# RSheet2.net
KiCad netlist of a schematic drawn in Altium Designer
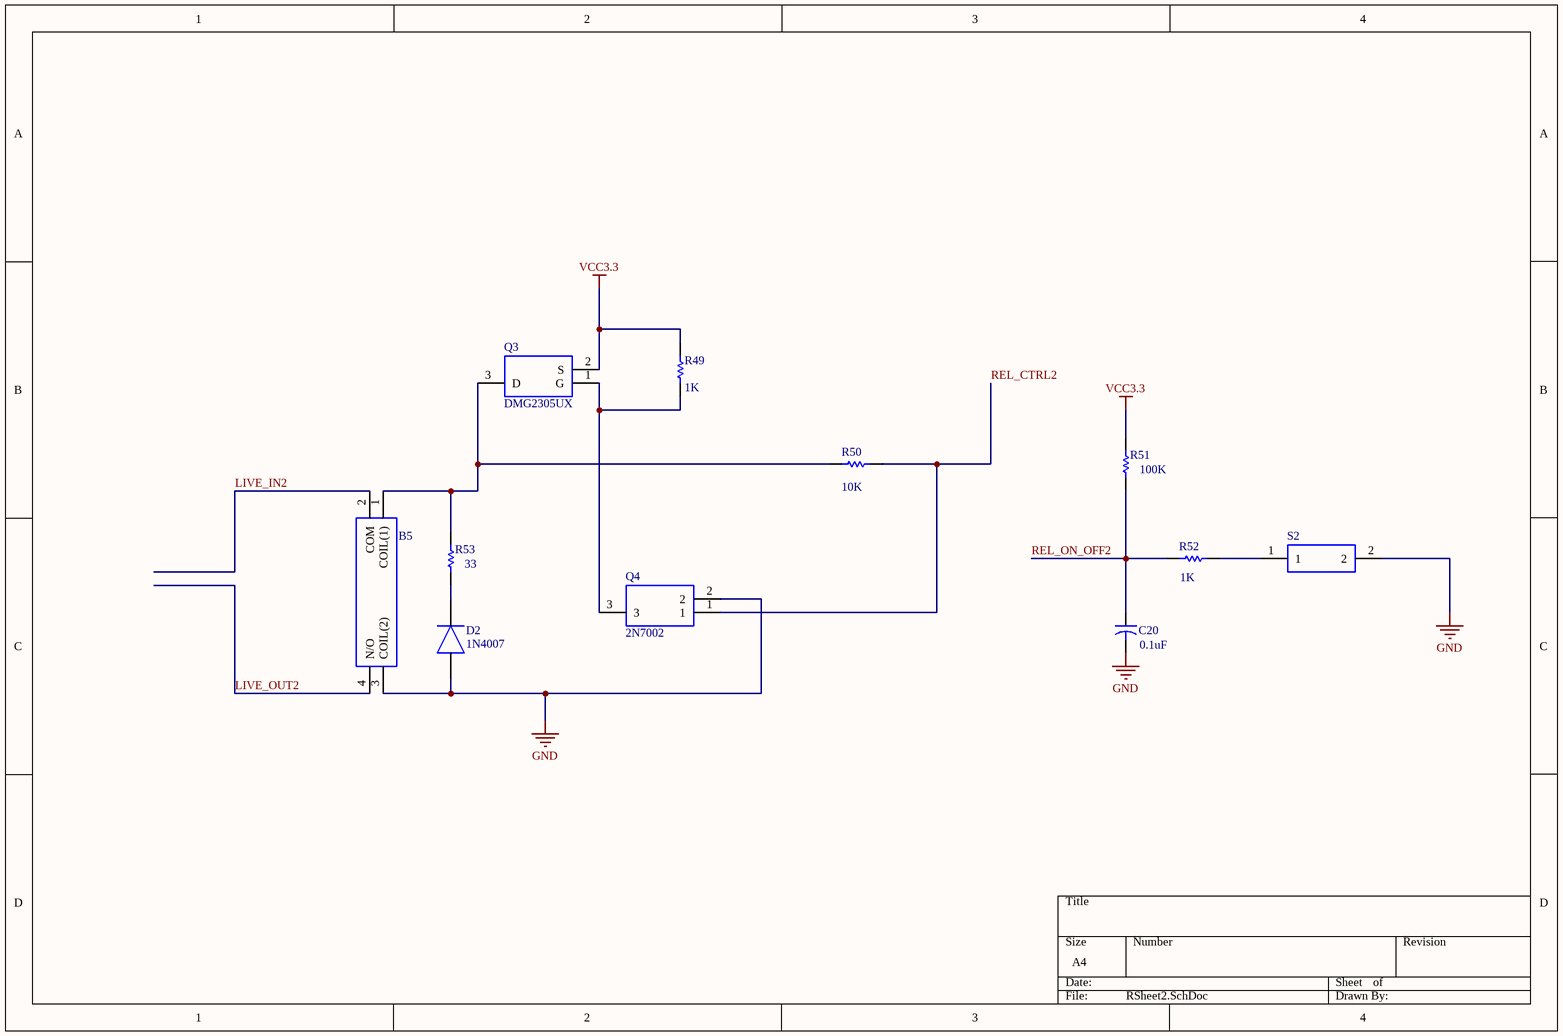
[diagram p0: RSheet2.SchDoc]

(export (version "E")
  (design (tool "Eeschema 10.0.6"))
  (components
    (comp (ref "B5")
      (value "HF3FA_005-HTF")
      (footprint "HF3FA005HTF:HF3FA005HTF")
      (description "Subminiature high power relay. 10A 5V.")
      (fields (field (name "MANUFACTURER_PART_NUMBER") "HF3FA/005-HTF"))
      (libsource (lib "HF3FA_005-HTF") (part "HF3FA_005-HTF"))
    )
    (comp (ref "C20")
      (value "0.1uF")
      (footprint "RESC0603X26N:RESC0603X26N")
      (description "Capacitor")
      (fields (field (name "Comment") "Cap2") (field (name "PUBLISHER") "Altium Limited"))
      (libsource (lib "Miscellaneous Devices") (part "Cap2"))
    )
    (comp (ref "D2")
      (value "1N4007")
      (footprint "DIOAD1408W86L464D236:DIOAD1408W86L464D236")
      (description "Diode Standard 1A 1000V 1Vf DO41 Diodes Inc 1N4007-T, Switching Diode, 1000V 1A, 2-Pin DO-41")
      (fields (field (name "RS PART NUMBER") "7384724P") (field (name "MANUFACTURER_PART_NUMBER") "1N4007-T"))
      (libsource (lib "1N4007-T") (part "1N4007-T"))
    )
    (comp (ref "Q3")
      (value "DMG2305UX")
      (footprint "SOT96P240X100-3N:SOT96P240X100-3N")
      (fields
        (field (name "RS PART NUMBER") "1219640")
        (field (name "MANUFACTURER_PART_NUMBER") "DMG2305UX-7")
      )
      (libsource (lib "DMG2305UX-7") (part "DMG2305UX-7"))
    )
    (comp (ref "Q4")
      (value "2N7002")
      (footprint "SOT95P230X110-3N:SOT95P230X110-3N")
      (fields
        (field (name "RS PART NUMBER") "1125526")
        (field (name "MANUFACTURER_PART_NUMBER") "2N7002,215")
      )
      (libsource (lib "2N7002_215") (part "2N7002_215"))
    )
    (comp (ref "R49")
      (value "1K")
      (footprint "AXIAL-0.3")
      (description "Resistor")
      (fields (field (name "Comment") "Res1") (field (name "PUBLISHER") "Altium Limited"))
      (libsource (lib "Miscellaneous Devices") (part "Res1"))
    )
    (comp (ref "R50")
      (value "10K")
      (footprint "AXIAL-0.3")
      (description "Resistor")
      (fields (field (name "Comment") "Res1") (field (name "PUBLISHER") "Altium Limited"))
      (libsource (lib "Miscellaneous Devices") (part "Res1"))
    )
    (comp (ref "R51")
      (value "100K")
      (footprint "RESC0603X26N:RESC0603X26N")
      (description "Resistor")
      (fields (field (name "Comment") "Res1") (field (name "PUBLISHER") "Altium Limited"))
      (libsource (lib "Miscellaneous Devices") (part "Res1"))
    )
    (comp (ref "R52")
      (value "1K")
      (footprint "RESC0603X26N:RESC0603X26N")
      (description "Resistor")
      (fields (field (name "Comment") "Res1") (field (name "PUBLISHER") "Altium Limited"))
      (libsource (lib "Miscellaneous Devices") (part "Res1"))
    )
    (comp (ref "R53")
      (value "33")
      (footprint "AXIAL-0.3")
      (description "Resistor")
      (fields (field (name "PUBLISHER") "Altium Limited"))
      (libsource (lib "Miscellaneous Devices") (part "Res1"))
    )
    (comp (ref "S2")
      (value "TL3330AF260QG")
      (footprint "SMD & J-Bend Tact Switch WS-TASV:434121043836")
      (description "Tactile Switches 50mA@12VDC 260g OF Silver contacts")
      (libsource (lib "TL3330AF260QG") (part "TL3330AF260QG"))
    )
  )
  (nets
    (net (code "1") (name "/LIVE_IN2") (class "Default")
      (node (ref "B5") (pin "2") (pinfunction "COM_2") (pintype "passive"))
    )
    (net (code "2") (name "/LIVE_OUT2") (class "Default")
      (node (ref "B5") (pin "4") (pinfunction "N/O_4") (pintype "passive"))
    )
    (net (code "3") (name "/REL_CTRL2") (class "Default")
      (node (ref "Q4") (pin "1") (pinfunction "1_1") (pintype "passive"))
      (node (ref "R50") (pin "2") (pinfunction "2_2") (pintype "passive"))
    )
    (net (code "4") (name "/REL_ON_OFF2") (class "Default")
      (node (ref "C20") (pin "1") (pinfunction "1_1") (pintype "passive"))
      (node (ref "R51") (pin "1") (pinfunction "1_1") (pintype "passive"))
      (node (ref "R52") (pin "1") (pinfunction "1_1") (pintype "passive"))
    )
    (net (code "5") (name "GND") (class "Default")
      (node (ref "B5") (pin "3") (pinfunction "COIL(2)_3") (pintype "passive"))
      (node (ref "C20") (pin "2") (pinfunction "2_2") (pintype "passive"))
      (node (ref "D2") (pin "2") (pinfunction "A_2") (pintype "passive"))
      (node (ref "Q4") (pin "2") (pinfunction "2_2") (pintype "passive"))
      (node (ref "S2") (pin "2") (pinfunction "2_2") (pintype "passive"))
    )
    (net (code "6") (name "Net-(B5-COIL(1))") (class "Default")
      (node (ref "B5") (pin "1") (pinfunction "COIL(1)_1") (pintype "passive"))
      (node (ref "Q3") (pin "3") (pinfunction "D_3") (pintype "passive"))
      (node (ref "R50") (pin "1") (pinfunction "1_1") (pintype "passive"))
      (node (ref "R53") (pin "2") (pinfunction "2_2") (pintype "passive"))
    )
    (net (code "7") (name "Net-(D2-K)") (class "Default")
      (node (ref "D2") (pin "1") (pinfunction "K_1") (pintype "passive"))
      (node (ref "R53") (pin "1") (pinfunction "1_1") (pintype "passive"))
    )
    (net (code "8") (name "Net-(Q3-G)") (class "Default")
      (node (ref "Q3") (pin "1") (pinfunction "G_1") (pintype "passive"))
      (node (ref "Q4") (pin "3") (pinfunction "3_3") (pintype "passive"))
      (node (ref "R49") (pin "1") (pinfunction "1_1") (pintype "passive"))
    )
    (net (code "9") (name "Net-(R52-Pad2)") (class "Default")
      (node (ref "R52") (pin "2") (pinfunction "2_2") (pintype "passive"))
      (node (ref "S2") (pin "1") (pinfunction "1_1") (pintype "passive"))
    )
    (net (code "10") (name "VCC3.3") (class "Default")
      (node (ref "Q3") (pin "2") (pinfunction "S_2") (pintype "passive"))
      (node (ref "R49") (pin "2") (pinfunction "2_2") (pintype "passive"))
      (node (ref "R51") (pin "2") (pinfunction "2_2") (pintype "passive"))
    )
  )
)
